# SeptinaryAI_Balldi__elec_plane__plane_20.net
KiCad netlist of a schematic drawn in Altium Designer
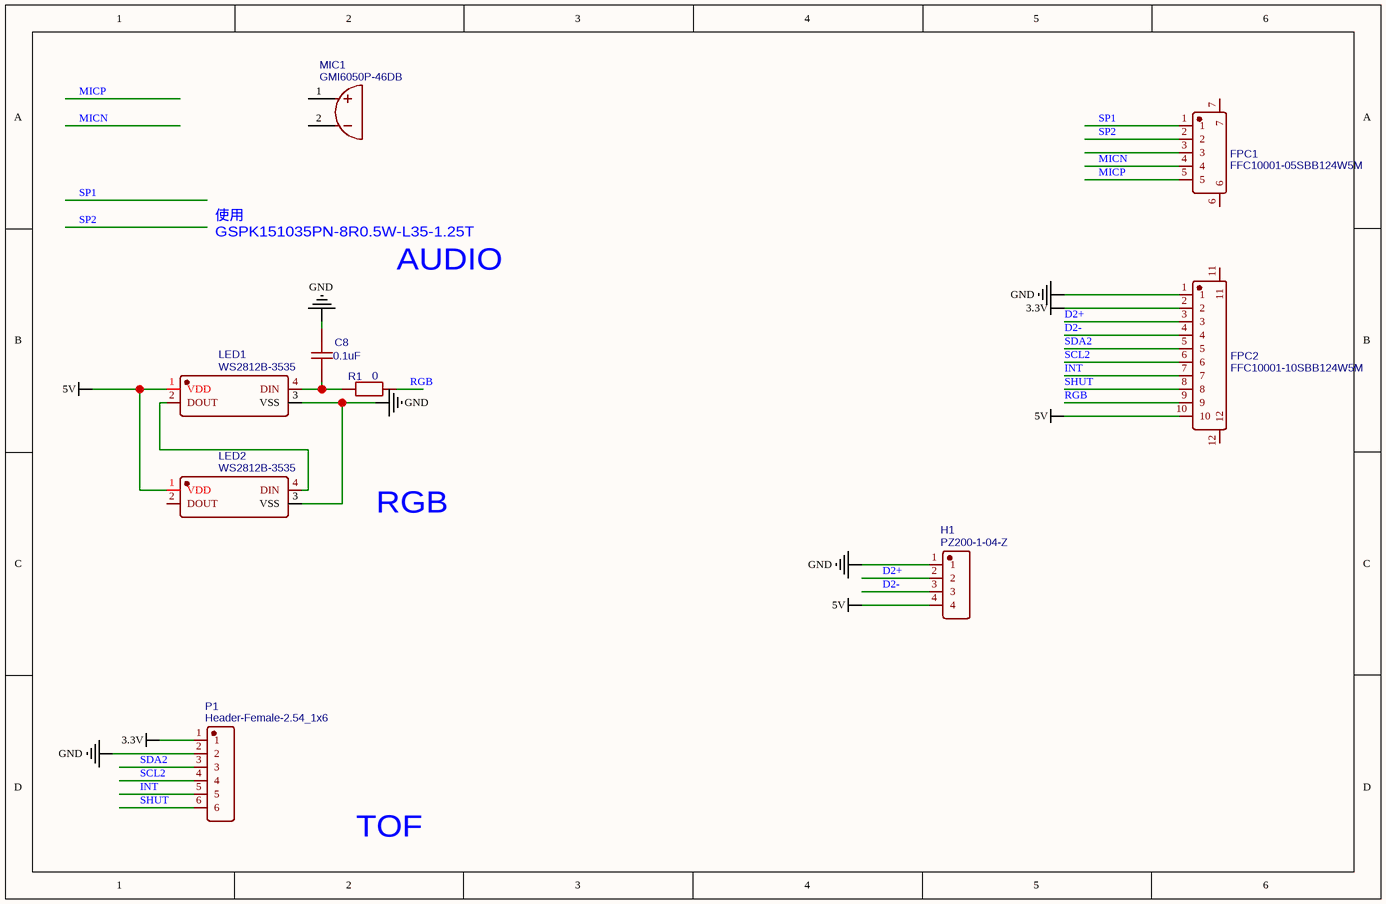
[diagram p0: SeptinaryAI_Balldi__elec_plane__plane_2023-07-21.schdoc]

(export (version "E")
  (design (tool "Eeschema 10.0.6"))
  (components
    (comp (ref "C8")
      (value "0.1uF")
      (fields
        (field (name "BOM_SUPPLIER PART") "C2762283")
        (field (name "BOM_MANUFACTURER PART") "CL10F104ZO8NNNC")
        (field (name "CONTRIBUTOR") "LCSC")
      )
      (libsource (lib "altium-import") (part "root_1_0.1uF_"))
    )
    (comp (ref "FPC1")
      (value "FFC10001-05SBB124W5M")
      (fields (field (name "BOM_SUPPLIER PART") "C2833987") (field (name "CONTRIBUTOR") "LCSC"))
      (libsource (lib "altium-import") (part "root_0_FFC10001-05SBB124W5M_"))
    )
    (comp (ref "FPC2")
      (value "FFC10001-10SBB124W5M")
      (fields (field (name "BOM_SUPPLIER PART") "C456461") (field (name "CONTRIBUTOR") "LCSC"))
      (libsource (lib "altium-import") (part "root_0_FFC10001-10SBB124W5M_"))
    )
    (comp (ref "H1")
      (value "PZ200-1-04-Z")
      (fields (field (name "BOM_SUPPLIER PART") "C2905950") (field (name "CONTRIBUTOR") "LCSC"))
      (libsource (lib "altium-import") (part "root_0_PZ200-1-04-Z_"))
    )
    (comp (ref "LED1")
      (value "WS2812B-3535")
      (fields (field (name "BOM_SUPPLIER PART") "C114583") (field (name "CONTRIBUTOR") "LCSC"))
      (libsource (lib "altium-import") (part "root_0_WS2812B-3535_"))
    )
    (comp (ref "LED2")
      (value "WS2812B-3535")
      (fields (field (name "BOM_SUPPLIER PART") "C114583") (field (name "CONTRIBUTOR") "LCSC"))
      (libsource (lib "altium-import") (part "root_0_WS2812B-3535_"))
    )
    (comp (ref "MIC1")
      (value "GMI6050P-46DB")
      (fields
        (field (name "BOM_SUPPLIER PART") "C233944")
        (field (name "BOM_MANUFACTURER PART") "GMI6050P-46db")
        (field (name "CONTRIBUTOR") "LCSC")
      )
      (libsource (lib "altium-import") (part "root_0_GMI6050P-46DB_"))
    )
    (comp (ref "P1")
      (value "Header-Female-2.54_1x6")
      (fields
        (field (name "BOM_MANUFACTURER PART") "Female header 1*6p")
        (field (name "BOM_SUPPLIER PART") "C40877")
      )
      (libsource (lib "altium-import") (part "root_0_Header-Female-2.54_1x6_"))
    )
    (comp (ref "R1")
      (value "0")
      (fields
        (field (name "BOM_SUPPLIER PART") "C1870287")
        (field (name "BOM_MANUFACTURER PART") "TNPW0603130RBEEA")
        (field (name "CONTRIBUTOR") "LCSC")
      )
      (libsource (lib "altium-import") (part "root_2_0_"))
    )
  )
  (nets
    (net (code "1") (name "/D2+") (class "Default")
      (node (ref "FPC2") (pin "3") (pinfunction "3_3") (pintype "passive"))
      (node (ref "H1") (pin "2") (pinfunction "2_2") (pintype "passive"))
    )
    (net (code "2") (name "/D2-") (class "Default")
      (node (ref "FPC2") (pin "4") (pinfunction "4_4") (pintype "passive"))
      (node (ref "H1") (pin "3") (pinfunction "3_3") (pintype "passive"))
    )
    (net (code "3") (name "/INT") (class "Default")
      (node (ref "FPC2") (pin "7") (pinfunction "7_7") (pintype "passive"))
      (node (ref "P1") (pin "5") (pinfunction "5_5") (pintype "passive"))
    )
    (net (code "4") (name "/MICN") (class "Default")
      (node (ref "FPC1") (pin "4") (pinfunction "4_4") (pintype "passive"))
    )
    (net (code "5") (name "/MICP") (class "Default")
      (node (ref "FPC1") (pin "5") (pinfunction "5_5") (pintype "passive"))
    )
    (net (code "6") (name "/RGB") (class "Default")
      (node (ref "FPC2") (pin "9") (pinfunction "9_9") (pintype "passive"))
      (node (ref "R1") (pin "1") (pinfunction "1_1") (pintype "passive"))
    )
    (net (code "7") (name "/SCL2") (class "Default")
      (node (ref "FPC2") (pin "6") (pinfunction "6_6") (pintype "passive"))
      (node (ref "P1") (pin "4") (pinfunction "4_4") (pintype "passive"))
    )
    (net (code "8") (name "/SDA2") (class "Default")
      (node (ref "FPC2") (pin "5") (pinfunction "5_5") (pintype "passive"))
      (node (ref "P1") (pin "3") (pinfunction "3_3") (pintype "passive"))
    )
    (net (code "9") (name "/SHUT") (class "Default")
      (node (ref "FPC2") (pin "8") (pinfunction "8_8") (pintype "passive"))
      (node (ref "P1") (pin "6") (pinfunction "6_6") (pintype "passive"))
    )
    (net (code "10") (name "/SP1") (class "Default")
      (node (ref "FPC1") (pin "1") (pinfunction "1_1") (pintype "passive"))
    )
    (net (code "11") (name "/SP2") (class "Default")
      (node (ref "FPC1") (pin "2") (pinfunction "2_2") (pintype "passive"))
    )
    (net (code "12") (name "3.3V") (class "Default")
      (node (ref "FPC2") (pin "2") (pinfunction "2_2") (pintype "passive"))
      (node (ref "P1") (pin "1") (pinfunction "1_1") (pintype "passive"))
    )
    (net (code "13") (name "5V") (class "Default")
      (node (ref "FPC2") (pin "10") (pinfunction "10_10") (pintype "passive"))
      (node (ref "H1") (pin "4") (pinfunction "4_4") (pintype "passive"))
      (node (ref "LED1") (pin "1") (pinfunction "VDD_1") (pintype "passive"))
      (node (ref "LED2") (pin "1") (pinfunction "VDD_1") (pintype "passive"))
    )
    (net (code "14") (name "GND") (class "Default")
      (node (ref "C8") (pin "2") (pinfunction "2_2") (pintype "passive"))
      (node (ref "FPC2") (pin "1") (pinfunction "1_1") (pintype "passive"))
      (node (ref "H1") (pin "1") (pinfunction "1_1") (pintype "passive"))
      (node (ref "LED1") (pin "3") (pinfunction "VSS_3") (pintype "passive"))
      (node (ref "LED2") (pin "3") (pinfunction "VSS_3") (pintype "passive"))
      (node (ref "P1") (pin "2") (pinfunction "2_2") (pintype "passive"))
    )
    (net (code "15") (name "Net-(LED1-DIN)") (class "Default")
      (node (ref "C8") (pin "1") (pinfunction "1_1") (pintype "passive"))
      (node (ref "LED1") (pin "4") (pinfunction "DIN_4") (pintype "passive"))
      (node (ref "R1") (pin "2") (pinfunction "2_2") (pintype "passive"))
    )
    (net (code "16") (name "Net-(LED1-DOUT)") (class "Default")
      (node (ref "LED1") (pin "2") (pinfunction "DOUT_2") (pintype "passive"))
      (node (ref "LED2") (pin "4") (pinfunction "DIN_4") (pintype "passive"))
    )
    (net (code "17") (name "unconnected-(FPC1-Pad3)") (class "Default")
      (node (ref "FPC1") (pin "3") (pinfunction "3_3") (pintype "passive"))
    )
    (net (code "18") (name "unconnected-(FPC1-Pad6)") (class "Default")
      (node (ref "FPC1") (pin "6") (pinfunction "6_6") (pintype "passive"))
    )
    (net (code "19") (name "unconnected-(FPC1-Pad7)") (class "Default")
      (node (ref "FPC1") (pin "7") (pinfunction "7_7") (pintype "passive"))
    )
    (net (code "20") (name "unconnected-(FPC2-Pad11)") (class "Default")
      (node (ref "FPC2") (pin "11") (pinfunction "11_11") (pintype "passive"))
    )
    (net (code "21") (name "unconnected-(FPC2-Pad12)") (class "Default")
      (node (ref "FPC2") (pin "12") (pinfunction "12_12") (pintype "passive"))
    )
    (net (code "22") (name "unconnected-(LED2-DOUT-Pad2)") (class "Default")
      (node (ref "LED2") (pin "2") (pinfunction "DOUT_2") (pintype "passive"))
    )
    (net (code "23") (name "unconnected-(MIC1-GND-Pad2)") (class "Default")
      (node (ref "MIC1") (pin "2") (pinfunction "GND_2") (pintype "passive"))
    )
    (net (code "24") (name "unconnected-(MIC1-output-Pad1)") (class "Default")
      (node (ref "MIC1") (pin "1") (pinfunction "output_1") (pintype "passive"))
    )
  )
)
